# Harness_Wrapper.net
KiCad netlist of a schematic drawn in Altium Designer
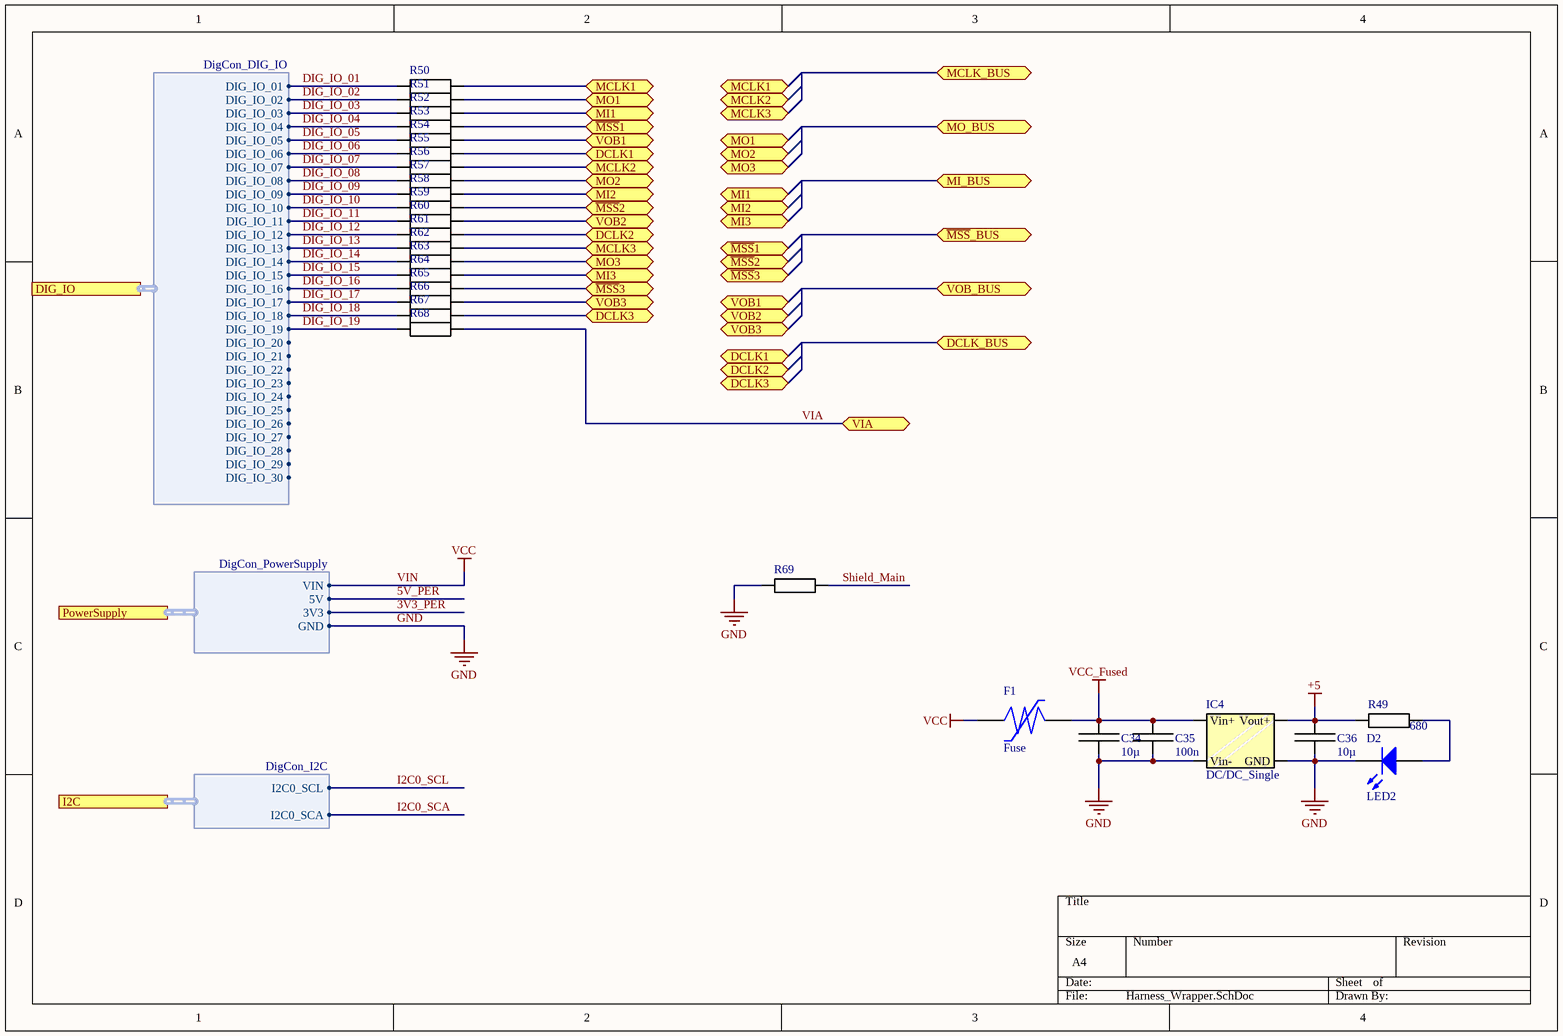
[diagram p0: Harness_Wrapper.SchDoc]

(export (version "E")
  (design (tool "Eeschema 10.0.6"))
  (components
    (comp (ref "C34")
      (value "10µ")
      (footprint "RLC_0805")
      (libsource (lib "PRJ_LIB_LTC2983_Card") (part "C"))
    )
    (comp (ref "C35")
      (value "100n")
      (footprint "RLC_0805")
      (libsource (lib "PRJ_LIB_LTC2983_Card") (part "C"))
    )
    (comp (ref "C36")
      (value "10µ")
      (footprint "RLC_0805")
      (libsource (lib "PRJ_LIB_LTC2983_Card") (part "C"))
    )
    (comp (ref "D2")
      (value "LED2")
      (footprint "3.2X1.6X1.1")
      (description "Typical RED, GREEN, YELLOW, AMBER GaAs LED")
      (fields (field (name "PUBLISHER") "Altium Limited"))
      (libsource (lib "Miscellaneous Devices") (part "LED2"))
    )
    (comp (ref "F1")
      (value "Fuse")
      (footprint "RLC_1812")
      (libsource (lib "PRJ_LIB_LTC2983_Card") (part "Fuse"))
    )
    (comp (ref "IC4")
      (value "DC/DC_Single")
      (footprint "SIP4DCDC")
      (libsource (lib "PRJ_LIB_LTC2983_Card") (part "DC/DC_Single"))
    )
    (comp (ref "R49")
      (value "680")
      (footprint "RLC_0805")
      (libsource (lib "PRJ_LIB_LTC2983_Card") (part "R"))
    )
    (comp (ref "R50")
      (value "100")
      (footprint "RLC_0805")
      (libsource (lib "PRJ_LIB_LTC2983_Card") (part "R"))
    )
    (comp (ref "R51")
      (value "100")
      (footprint "RLC_0805")
      (libsource (lib "PRJ_LIB_LTC2983_Card") (part "R"))
    )
    (comp (ref "R52")
      (value "100")
      (footprint "RLC_0805")
      (libsource (lib "PRJ_LIB_LTC2983_Card") (part "R"))
    )
    (comp (ref "R53")
      (value "100")
      (footprint "RLC_0805")
      (libsource (lib "PRJ_LIB_LTC2983_Card") (part "R"))
    )
    (comp (ref "R54")
      (value "100")
      (footprint "RLC_0805")
      (libsource (lib "PRJ_LIB_LTC2983_Card") (part "R"))
    )
    (comp (ref "R55")
      (value "100")
      (footprint "RLC_0805")
      (libsource (lib "PRJ_LIB_LTC2983_Card") (part "R"))
    )
    (comp (ref "R56")
      (value "100")
      (footprint "RLC_0805")
      (libsource (lib "PRJ_LIB_LTC2983_Card") (part "R"))
    )
    (comp (ref "R57")
      (value "100")
      (footprint "RLC_0805")
      (libsource (lib "PRJ_LIB_LTC2983_Card") (part "R"))
    )
    (comp (ref "R58")
      (value "100")
      (footprint "RLC_0805")
      (libsource (lib "PRJ_LIB_LTC2983_Card") (part "R"))
    )
    (comp (ref "R59")
      (value "100")
      (footprint "RLC_0805")
      (libsource (lib "PRJ_LIB_LTC2983_Card") (part "R"))
    )
    (comp (ref "R60")
      (value "100")
      (footprint "RLC_0805")
      (libsource (lib "PRJ_LIB_LTC2983_Card") (part "R"))
    )
    (comp (ref "R61")
      (value "100")
      (footprint "RLC_0805")
      (libsource (lib "PRJ_LIB_LTC2983_Card") (part "R"))
    )
    (comp (ref "R62")
      (value "100")
      (footprint "RLC_0805")
      (libsource (lib "PRJ_LIB_LTC2983_Card") (part "R"))
    )
    (comp (ref "R63")
      (value "100")
      (footprint "RLC_0805")
      (libsource (lib "PRJ_LIB_LTC2983_Card") (part "R"))
    )
    (comp (ref "R64")
      (value "100")
      (footprint "RLC_0805")
      (libsource (lib "PRJ_LIB_LTC2983_Card") (part "R"))
    )
    (comp (ref "R65")
      (value "100")
      (footprint "RLC_0805")
      (libsource (lib "PRJ_LIB_LTC2983_Card") (part "R"))
    )
    (comp (ref "R66")
      (value "100")
      (footprint "RLC_0805")
      (libsource (lib "PRJ_LIB_LTC2983_Card") (part "R"))
    )
    (comp (ref "R67")
      (value "100")
      (footprint "RLC_0805")
      (libsource (lib "PRJ_LIB_LTC2983_Card") (part "R"))
    )
    (comp (ref "R68")
      (value "100")
      (footprint "RLC_0805")
      (libsource (lib "PRJ_LIB_LTC2983_Card") (part "R"))
    )
    (comp (ref "R69") (value "0") (footprint "RLC_0805") (libsource (lib "PRJ_LIB_LTC2983_Card") (part "R")))
  )
  (nets
    (net (code "4") (name "+5") (class "Default")
      (node (ref "C36") (pin "1") (pinfunction "1_1") (pintype "passive"))
      (node (ref "IC4") (pin "6") (pinfunction "Vout+_6") (pintype "passive"))
      (node (ref "R49") (pin "1") (pinfunction "1_1") (pintype "passive"))
    )
    (net (code "7") (name "/DCLK1") (class "Default")
      (node (ref "R55") (pin "2") (pinfunction "2_2") (pintype "passive"))
    )
    (net (code "8") (name "/DCLK2") (class "Default")
      (node (ref "R61") (pin "2") (pinfunction "2_2") (pintype "passive"))
    )
    (net (code "9") (name "/DCLK3") (class "Default")
      (node (ref "R67") (pin "2") (pinfunction "2_2") (pintype "passive"))
    )
    (net (code "11") (name "/DIG_IO_01") (class "Default")
      (node (ref "R50") (pin "1") (pinfunction "1_1") (pintype "passive"))
    )
    (net (code "12") (name "/DIG_IO_02") (class "Default")
      (node (ref "R51") (pin "1") (pinfunction "1_1") (pintype "passive"))
    )
    (net (code "13") (name "/DIG_IO_03") (class "Default")
      (node (ref "R52") (pin "1") (pinfunction "1_1") (pintype "passive"))
    )
    (net (code "14") (name "/DIG_IO_04") (class "Default")
      (node (ref "R53") (pin "1") (pinfunction "1_1") (pintype "passive"))
    )
    (net (code "15") (name "/DIG_IO_05") (class "Default")
      (node (ref "R54") (pin "1") (pinfunction "1_1") (pintype "passive"))
    )
    (net (code "16") (name "/DIG_IO_06") (class "Default")
      (node (ref "R55") (pin "1") (pinfunction "1_1") (pintype "passive"))
    )
    (net (code "17") (name "/DIG_IO_07") (class "Default")
      (node (ref "R56") (pin "1") (pinfunction "1_1") (pintype "passive"))
    )
    (net (code "18") (name "/DIG_IO_08") (class "Default")
      (node (ref "R57") (pin "1") (pinfunction "1_1") (pintype "passive"))
    )
    (net (code "19") (name "/DIG_IO_09") (class "Default")
      (node (ref "R58") (pin "1") (pinfunction "1_1") (pintype "passive"))
    )
    (net (code "20") (name "/DIG_IO_10") (class "Default")
      (node (ref "R59") (pin "1") (pinfunction "1_1") (pintype "passive"))
    )
    (net (code "21") (name "/DIG_IO_11") (class "Default")
      (node (ref "R60") (pin "1") (pinfunction "1_1") (pintype "passive"))
    )
    (net (code "22") (name "/DIG_IO_12") (class "Default")
      (node (ref "R61") (pin "1") (pinfunction "1_1") (pintype "passive"))
    )
    (net (code "23") (name "/DIG_IO_13") (class "Default")
      (node (ref "R62") (pin "1") (pinfunction "1_1") (pintype "passive"))
    )
    (net (code "24") (name "/DIG_IO_14") (class "Default")
      (node (ref "R63") (pin "1") (pinfunction "1_1") (pintype "passive"))
    )
    (net (code "25") (name "/DIG_IO_15") (class "Default")
      (node (ref "R64") (pin "1") (pinfunction "1_1") (pintype "passive"))
    )
    (net (code "26") (name "/DIG_IO_16") (class "Default")
      (node (ref "R65") (pin "1") (pinfunction "1_1") (pintype "passive"))
    )
    (net (code "27") (name "/DIG_IO_17") (class "Default")
      (node (ref "R66") (pin "1") (pinfunction "1_1") (pintype "passive"))
    )
    (net (code "28") (name "/DIG_IO_18") (class "Default")
      (node (ref "R67") (pin "1") (pinfunction "1_1") (pintype "passive"))
    )
    (net (code "29") (name "/DIG_IO_19") (class "Default")
      (node (ref "R68") (pin "1") (pinfunction "1_1") (pintype "passive"))
    )
    (net (code "32") (name "/MCLK1") (class "Default")
      (node (ref "R50") (pin "2") (pinfunction "2_2") (pintype "passive"))
    )
    (net (code "33") (name "/MCLK2") (class "Default")
      (node (ref "R56") (pin "2") (pinfunction "2_2") (pintype "passive"))
    )
    (net (code "34") (name "/MCLK3") (class "Default")
      (node (ref "R62") (pin "2") (pinfunction "2_2") (pintype "passive"))
    )
    (net (code "36") (name "/MI1") (class "Default")
      (node (ref "R52") (pin "2") (pinfunction "2_2") (pintype "passive"))
    )
    (net (code "37") (name "/MI2") (class "Default")
      (node (ref "R58") (pin "2") (pinfunction "2_2") (pintype "passive"))
    )
    (net (code "38") (name "/MI3") (class "Default")
      (node (ref "R64") (pin "2") (pinfunction "2_2") (pintype "passive"))
    )
    (net (code "40") (name "/MO1") (class "Default")
      (node (ref "R51") (pin "2") (pinfunction "2_2") (pintype "passive"))
    )
    (net (code "41") (name "/MO2") (class "Default")
      (node (ref "R57") (pin "2") (pinfunction "2_2") (pintype "passive"))
    )
    (net (code "42") (name "/MO3") (class "Default")
      (node (ref "R63") (pin "2") (pinfunction "2_2") (pintype "passive"))
    )
    (net (code "44") (name "/Shield_Main") (class "Default")
      (node (ref "R69") (pin "2") (pinfunction "2_2") (pintype "passive"))
    )
    (net (code "45") (name "/VIA") (class "Default")
      (node (ref "R68") (pin "2") (pinfunction "2_2") (pintype "passive"))
    )
    (net (code "46") (name "/VOB1") (class "Default")
      (node (ref "R54") (pin "2") (pinfunction "2_2") (pintype "passive"))
    )
    (net (code "47") (name "/VOB2") (class "Default")
      (node (ref "R60") (pin "2") (pinfunction "2_2") (pintype "passive"))
    )
    (net (code "48") (name "/VOB3") (class "Default")
      (node (ref "R66") (pin "2") (pinfunction "2_2") (pintype "passive"))
    )
    (net (code "53") (name "/~{MSS}1") (class "Default")
      (node (ref "R53") (pin "2") (pinfunction "2_2") (pintype "passive"))
    )
    (net (code "54") (name "/~{MSS}2") (class "Default")
      (node (ref "R59") (pin "2") (pinfunction "2_2") (pintype "passive"))
    )
    (net (code "55") (name "/~{MSS}3") (class "Default")
      (node (ref "R65") (pin "2") (pinfunction "2_2") (pintype "passive"))
    )
    (net (code "57") (name "GND") (class "Default")
      (node (ref "C34") (pin "2") (pinfunction "2_2") (pintype "passive"))
      (node (ref "C35") (pin "2") (pinfunction "2_2") (pintype "passive"))
      (node (ref "C36") (pin "2") (pinfunction "2_2") (pintype "passive"))
      (node (ref "D2") (pin "2") (pinfunction "K_2") (pintype "passive"))
      (node (ref "IC4") (pin "2") (pinfunction "Vin-_2") (pintype "passive"))
      (node (ref "IC4") (pin "4") (pinfunction "GND_4") (pintype "passive"))
      (node (ref "R69") (pin "1") (pinfunction "1_1") (pintype "passive"))
    )
    (net (code "58") (name "Net-(D2-A)") (class "Default")
      (node (ref "D2") (pin "1") (pinfunction "A_1") (pintype "passive"))
      (node (ref "R49") (pin "2") (pinfunction "2_2") (pintype "passive"))
    )
    (net (code "59") (name "VCC") (class "Default")
      (node (ref "F1") (pin "1") (pinfunction "1_1") (pintype "passive"))
    )
    (net (code "60") (name "VCC_Fused") (class "Default")
      (node (ref "C34") (pin "1") (pinfunction "1_1") (pintype "passive"))
      (node (ref "C35") (pin "1") (pinfunction "1_1") (pintype "passive"))
      (node (ref "F1") (pin "2") (pinfunction "2_2") (pintype "passive"))
      (node (ref "IC4") (pin "1") (pinfunction "Vin+_1") (pintype "passive"))
    )
  )
)
